# Sheet1.net
KiCad netlist of a schematic drawn in Altium Designer
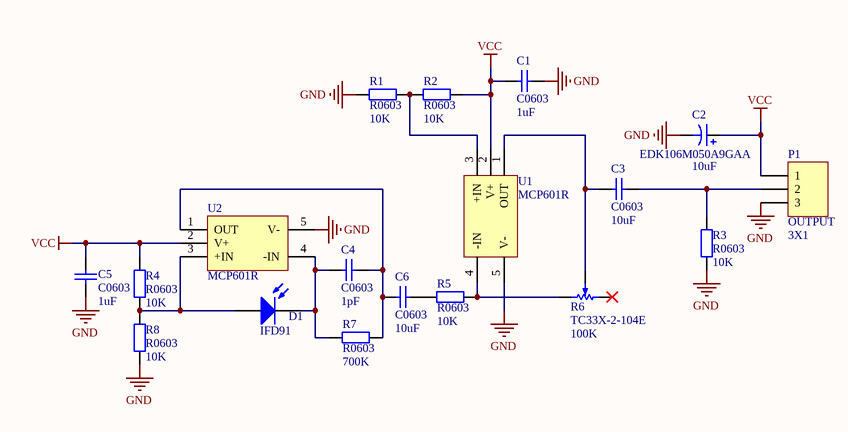
[diagram p0: Sheet1.SchDoc]

(export (version "E")
  (design (tool "Eeschema 10.0.6"))
  (components
    (comp (ref "C1")
      (value "C0603")
      (footprint "1608[0603]")
      (description "Ceramic Capacitor")
      (fields (field (name "ALTIUM_VALUE") "1uF"))
      (libsource (lib "Miscellaneous Devices Local Copy") (part "Cap"))
    )
    (comp (ref "C2")
      (value "EDK106M050A9GAA")
      (footprint "EDK106M050A9GAA")
      (description "Aluminium Electrolytic Capacitor")
      (fields (field (name "ALTIUM_VALUE") "10uF"))
      (libsource (lib "Miscellaneous Devices Local Copy") (part "Cap Pol1"))
    )
    (comp (ref "C3")
      (value "C0603")
      (footprint "1608[0603]")
      (description "Ceramic Capacitor")
      (fields (field (name "ALTIUM_VALUE") "10uF"))
      (libsource (lib "Miscellaneous Devices Local Copy") (part "Cap"))
    )
    (comp (ref "C4")
      (value "C0603")
      (footprint "1608[0603]")
      (description "Ceramic Capacitor")
      (fields (field (name "ALTIUM_VALUE") "1pF"))
      (libsource (lib "Miscellaneous Devices Local Copy") (part "Cap"))
    )
    (comp (ref "C5")
      (value "C0603")
      (footprint "1608[0603]")
      (description "Ceramic Capacitor")
      (fields (field (name "ALTIUM_VALUE") "1uF"))
      (libsource (lib "Miscellaneous Devices Local Copy") (part "Cap"))
    )
    (comp (ref "C6")
      (value "C0603")
      (footprint "1608[0603]")
      (description "Ceramic Capacitor")
      (fields (field (name "ALTIUM_VALUE") "10uF"))
      (libsource (lib "Miscellaneous Devices Local Copy") (part "Cap"))
    )
    (comp (ref "D1")
      (value "IFD91")
      (footprint "IFD91")
      (description "Fotodiode For PMMA")
      (libsource (lib "Schlib1") (part "IFD91"))
    )
    (comp (ref "P1")
      (value "OUTPUT")
      (footprint "HDR1X3")
      (description "Header, 3-Pin")
      (fields (field (name "ALTIUM_VALUE") "3X1"))
      (libsource (lib "Miscellaneous Connectors Local Copy") (part "Header 3"))
    )
    (comp (ref "R1")
      (value "R0603")
      (footprint "J1-0603")
      (description "Resistor")
      (fields (field (name "ALTIUM_VALUE") "10K"))
      (libsource (lib "") (part "Res2_2"))
    )
    (comp (ref "R2")
      (value "R0603")
      (footprint "J1-0603")
      (description "Resistor")
      (fields (field (name "ALTIUM_VALUE") "10K"))
      (libsource (lib "") (part "Res2_2"))
    )
    (comp (ref "R3")
      (value "R0603")
      (footprint "J1-0603")
      (description "Resistor")
      (fields (field (name "ALTIUM_VALUE") "10K"))
      (libsource (lib "Miscellaneous Devices Local Copy") (part "Res2"))
    )
    (comp (ref "R4")
      (value "R0603")
      (footprint "J1-0603")
      (description "Resistor")
      (fields (field (name "ALTIUM_VALUE") "10K"))
      (libsource (lib "Miscellaneous Devices Local Copy") (part "Res2"))
    )
    (comp (ref "R5")
      (value "R0603")
      (footprint "J1-0603")
      (description "Resistor")
      (fields (field (name "ALTIUM_VALUE") "10K"))
      (libsource (lib "") (part "Res2_2"))
    )
    (comp (ref "R6")
      (value "TC33X-2-104E")
      (footprint "TC33X-2-104E")
      (description "Potentiometer")
      (fields (field (name "ALTIUM_VALUE") "100K"))
      (libsource (lib "Schlib1") (part "TC33X-2-104E"))
    )
    (comp (ref "R7")
      (value "R0603")
      (footprint "J1-0603")
      (description "Resistor")
      (fields (field (name "ALTIUM_VALUE") "700K"))
      (libsource (lib "") (part "Res2_2"))
    )
    (comp (ref "R8")
      (value "R0603")
      (footprint "J1-0603")
      (description "Resistor")
      (fields (field (name "ALTIUM_VALUE") "10K"))
      (libsource (lib "") (part "Res2_1"))
    )
    (comp (ref "U1")
      (value "MCP601R")
      (footprint "MCP601_SOT23")
      (description "Single Supply Operational Amplifier")
      (libsource (lib "Schlib1") (part "MCP601R"))
    )
    (comp (ref "U2")
      (value "MCP601R")
      (footprint "MCP601_SOT23")
      (description "Single Supply Operational Amplifier")
      (libsource (lib "") (part "MCP601R_1"))
    )
  )
  (nets
    (net (code "1") (name "GND") (class "Default")
      (node (ref "C1") (pin "2") (pinfunction "2_2") (pintype "passive"))
      (node (ref "C2") (pin "2") (pinfunction "2_2") (pintype "passive"))
      (node (ref "C5") (pin "2") (pinfunction "2_2") (pintype "passive"))
      (node (ref "P1") (pin "3") (pinfunction "3_3") (pintype "passive"))
      (node (ref "R1") (pin "2") (pinfunction "2_2") (pintype "passive"))
      (node (ref "R3") (pin "2") (pinfunction "2_2") (pintype "passive"))
      (node (ref "R8") (pin "1") (pinfunction "1_1") (pintype "passive"))
      (node (ref "U1") (pin "5") (pinfunction "V-_5") (pintype "passive"))
      (node (ref "U2") (pin "5") (pinfunction "V-_5") (pintype "passive"))
    )
    (net (code "2") (name "Net-(C3-Pad2)") (class "Default")
      (node (ref "C3") (pin "2") (pinfunction "2_2") (pintype "passive"))
      (node (ref "P1") (pin "2") (pinfunction "2_2") (pintype "passive"))
      (node (ref "R3") (pin "1") (pinfunction "1_1") (pintype "passive"))
    )
    (net (code "3") (name "Net-(C6-Pad2)") (class "Default")
      (node (ref "C6") (pin "2") (pinfunction "2_2") (pintype "passive"))
      (node (ref "R5") (pin "2") (pinfunction "2_2") (pintype "passive"))
    )
    (net (code "4") (name "Net-(D1-A)") (class "Default")
      (node (ref "D1") (pin "2") (pinfunction "A_2") (pintype "passive"))
      (node (ref "R4") (pin "2") (pinfunction "2_2") (pintype "passive"))
      (node (ref "R8") (pin "2") (pinfunction "2_2") (pintype "passive"))
      (node (ref "U2") (pin "3") (pinfunction "+IN_3") (pintype "passive"))
    )
    (net (code "5") (name "Net-(D1-K)") (class "Default")
      (node (ref "C4") (pin "1") (pinfunction "1_1") (pintype "passive"))
      (node (ref "D1") (pin "1") (pinfunction "K_1") (pintype "passive"))
      (node (ref "R7") (pin "2") (pinfunction "2_2") (pintype "passive"))
      (node (ref "U2") (pin "4") (pinfunction "-IN_4") (pintype "passive"))
    )
    (net (code "6") (name "Net-(R6-+)") (class "Default")
      (node (ref "R5") (pin "1") (pinfunction "1_1") (pintype "passive"))
      (node (ref "R6") (pin "1") (pinfunction "+_1") (pintype "passive"))
      (node (ref "U1") (pin "4") (pinfunction "-IN_4") (pintype "passive"))
    )
    (net (code "7") (name "Net-(R6-W)") (class "Default")
      (node (ref "C3") (pin "1") (pinfunction "1_1") (pintype "passive"))
      (node (ref "R6") (pin "2") (pinfunction "W_2") (pintype "passive"))
      (node (ref "U1") (pin "1") (pinfunction "OUT_1") (pintype "passive"))
    )
    (net (code "8") (name "Net-(U1-+IN)") (class "Default")
      (node (ref "R1") (pin "1") (pinfunction "1_1") (pintype "passive"))
      (node (ref "R2") (pin "2") (pinfunction "2_2") (pintype "passive"))
      (node (ref "U1") (pin "3") (pinfunction "+IN_3") (pintype "passive"))
    )
    (net (code "9") (name "Net-(U2-OUT)") (class "Default")
      (node (ref "C4") (pin "2") (pinfunction "2_2") (pintype "passive"))
      (node (ref "C6") (pin "1") (pinfunction "1_1") (pintype "passive"))
      (node (ref "R7") (pin "1") (pinfunction "1_1") (pintype "passive"))
      (node (ref "U2") (pin "1") (pinfunction "OUT_1") (pintype "passive"))
    )
    (net (code "10") (name "VCC") (class "Default")
      (node (ref "C1") (pin "1") (pinfunction "1_1") (pintype "passive"))
      (node (ref "C2") (pin "1") (pinfunction "1_1") (pintype "passive"))
      (node (ref "C5") (pin "1") (pinfunction "1_1") (pintype "passive"))
      (node (ref "P1") (pin "1") (pinfunction "1_1") (pintype "passive"))
      (node (ref "R2") (pin "1") (pinfunction "1_1") (pintype "passive"))
      (node (ref "R4") (pin "1") (pinfunction "1_1") (pintype "passive"))
      (node (ref "U1") (pin "2") (pinfunction "V+_2") (pintype "passive"))
      (node (ref "U2") (pin "2") (pinfunction "V+_2") (pintype "passive"))
    )
    (net (code "11") (name "unconnected-(R6---Pad3)") (class "Default")
      (node (ref "R6") (pin "3") (pinfunction "-_3") (pintype "passive+no_connect"))
    )
  )
)
